# PX4FMUv2_4_6_3.net
KiCad netlist of a schematic drawn in Altium Designer
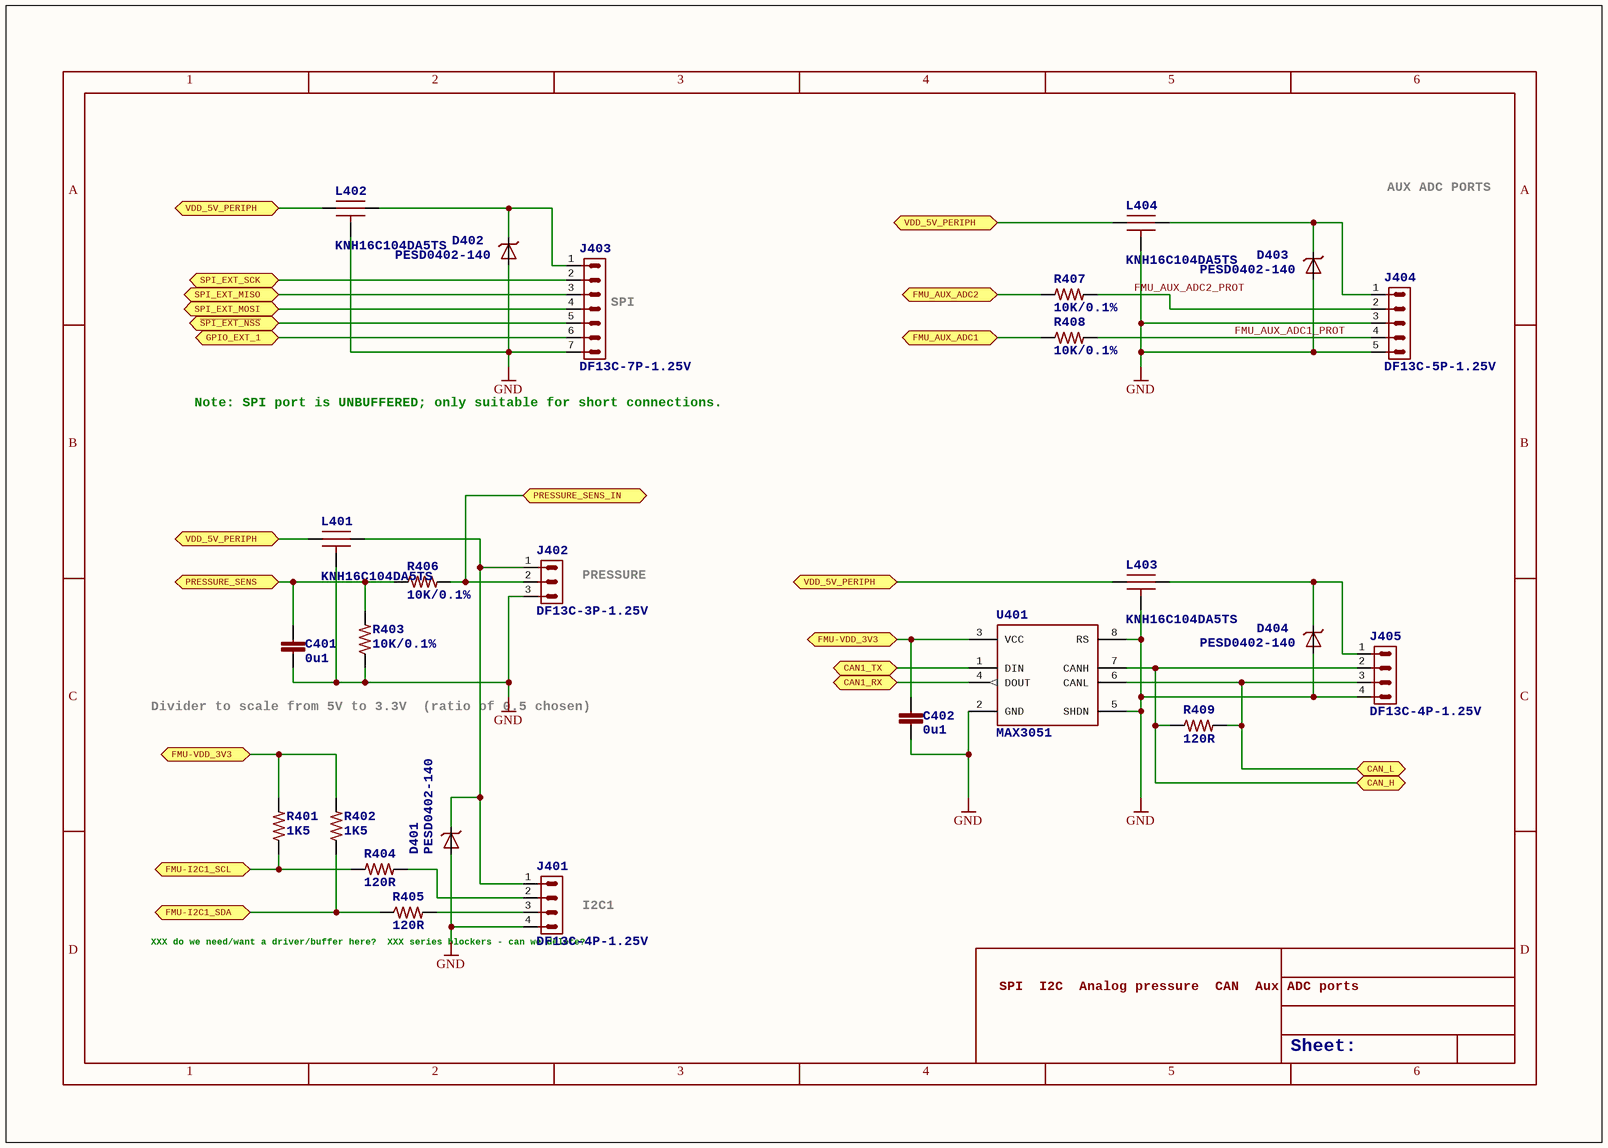
[diagram p0: PX4FMUv2.4.6_3.SchDoc]

(export (version "E")
  (design (tool "Eeschema 10.0.6"))
  (components
    (comp (ref "C401")
      (value "0u1")
      (footprint "0402-CAP")
      (description "CapacitorStandard 0603 ceramic capacitor, and 0.1\" leaded capacitor.")
      (fields (field (name "PARTNO") "CC0402ZRY5V7BB104"))
      (libsource (lib "pixhawk2") (part "CAP0402"))
    )
    (comp (ref "C402")
      (value "0u1")
      (footprint "0402-CAP")
      (description "CapacitorStandard 0603 ceramic capacitor, and 0.1\" leaded capacitor.")
      (fields (field (name "PARTNO") "CC0402ZRY5V7BB104"))
      (libsource (lib "pixhawk2") (part "CAP0402"))
    )
    (comp (ref "D401")
      (value "PESD0402-140")
      (footprint "0402-TVS")
      (libsource (lib "pixhawk2") (part "DIODE-TVS"))
    )
    (comp (ref "D402")
      (value "PESD0402-140")
      (footprint "0402-TVS")
      (libsource (lib "pixhawk2") (part "DIODE-TVS"))
    )
    (comp (ref "D403")
      (value "PESD0402-140")
      (footprint "0402-TVS")
      (libsource (lib "pixhawk2") (part "DIODE-TVS"))
    )
    (comp (ref "D404")
      (value "PESD0402-140")
      (footprint "0402-TVS")
      (libsource (lib "pixhawk2") (part "DIODE-TVS"))
    )
    (comp (ref "J401")
      (value "DF13C-4P-1.25V")
      (footprint "DF13C-4P-1.25V")
      (description "DF13-4P 1.25mm Pitch Miniature Crimping Connector.")
      (fields (field (name "PARTNO") "DF13C-4P-1.25V(20)"))
      (libsource (lib "con-hirose-df13") (part "DF13-4P-1.25V"))
    )
    (comp (ref "J402")
      (value "DF13C-3P-1.25V")
      (footprint "DF13C-3P-1.25V")
      (description "DF13-3P 1.25mm Pitch Miniature Crimping Connector.")
      (fields (field (name "PARTNO") "DF13C-3P-1.25V(20)"))
      (libsource (lib "con-hirose-df13") (part "DF13-3P-1.25V"))
    )
    (comp (ref "J403")
      (value "DF13C-7P-1.25V")
      (footprint "DF13C-7P-1.25V")
      (description "DF13-7P 1.25mm Pitch Miniature Crimping Connector.")
      (fields (field (name "PARTNO") "DF13C-7P-1.25V(20)"))
      (libsource (lib "con-hirose-df13") (part "DF13-7P-1.25V"))
    )
    (comp (ref "J404")
      (value "DF13C-5P-1.25V")
      (footprint "DF13C-5P-1.25V")
      (description "DF13-5P 1.25mm Pitch Miniature Crimping Connector.")
      (fields (field (name "PARTNO") "DF13C-5P-1.25V(20)"))
      (libsource (lib "con-hirose-df13") (part "DF13-5P-1.25V"))
    )
    (comp (ref "J405")
      (value "DF13C-4P-1.25V")
      (footprint "DF13C-4P-1.25V")
      (description "DF13-4P 1.25mm Pitch Miniature Crimping Connector.")
      (fields (field (name "PARTNO") "DF13C-4P-1.25V(20)"))
      (libsource (lib "con-hirose-df13") (part "DF13-4P-1.25V"))
    )
    (comp (ref "L401")
      (value "KNH16C104DA5TS")
      (footprint "KYOCERA-KNH16-DA")
      (description "Kyocera KNH16C104DA5TS EMI filter")
      (libsource (lib "pixhawk2") (part "KNH16C104DA5TS"))
    )
    (comp (ref "L402")
      (value "KNH16C104DA5TS")
      (footprint "KYOCERA-KNH16-DA")
      (description "Kyocera KNH16C104DA5TS EMI filter")
      (libsource (lib "pixhawk2") (part "KNH16C104DA5TS"))
    )
    (comp (ref "L403")
      (value "KNH16C104DA5TS")
      (footprint "KYOCERA-KNH16-DA")
      (description "Kyocera KNH16C104DA5TS EMI filter")
      (libsource (lib "pixhawk2") (part "KNH16C104DA5TS"))
    )
    (comp (ref "L404")
      (value "KNH16C104DA5TS")
      (footprint "KYOCERA-KNH16-DA")
      (description "Kyocera KNH16C104DA5TS EMI filter")
      (libsource (lib "pixhawk2") (part "KNH16C104DA5TS"))
    )
    (comp (ref "R401")
      (value "1K5")
      (footprint "0402-RES")
      (fields (field (name "PARTNO") "RC0402FR-071K5L"))
      (libsource (lib "pixhawk2") (part "RESISTOR0402-RES"))
    )
    (comp (ref "R402")
      (value "1K5")
      (footprint "0402-RES")
      (fields (field (name "PARTNO") "RC0402FR-071K5L"))
      (libsource (lib "pixhawk2") (part "RESISTOR0402-RES"))
    )
    (comp (ref "R403")
      (value "10K/0.1%")
      (footprint "0402-RES")
      (fields (field (name "PARTNO") "ERA-2AEB103X"))
      (libsource (lib "pixhawk2") (part "RESISTOR0402-RES"))
    )
    (comp (ref "R404")
      (value "120R")
      (footprint "0402-RES")
      (fields (field (name "PARTNO") "RC0402FR-07120RL"))
      (libsource (lib "pixhawk2") (part "RESISTOR0402-RES"))
    )
    (comp (ref "R405")
      (value "120R")
      (footprint "0402-RES")
      (fields (field (name "PARTNO") "RC0402FR-07120RL"))
      (libsource (lib "pixhawk2") (part "RESISTOR0402-RES"))
    )
    (comp (ref "R406")
      (value "10K/0.1%")
      (footprint "0402-RES")
      (fields (field (name "PARTNO") "ERA-2AEB103X"))
      (libsource (lib "pixhawk2") (part "RESISTOR0402-RES"))
    )
    (comp (ref "R407")
      (value "10K/0.1%")
      (footprint "0402-RES")
      (fields (field (name "PARTNO") "ERA-2AEB103X"))
      (libsource (lib "pixhawk2") (part "RESISTOR0402-RES"))
    )
    (comp (ref "R408")
      (value "10K/0.1%")
      (footprint "0402-RES")
      (fields (field (name "PARTNO") "ERA-2AEB103X"))
      (libsource (lib "pixhawk2") (part "RESISTOR0402-RES"))
    )
    (comp (ref "R409")
      (value "120R")
      (footprint "0402-RES")
      (fields (field (name "PARTNO") "RC0402FR-07120RL"))
      (libsource (lib "pixhawk2") (part "RESISTOR0402-RES"))
    )
    (comp (ref "U401")
      (value "MAX3051")
      (footprint "SOT23-8")
      (description "3.3-V CAN TRANSCEIVER")
      (fields (field (name "PARTNO") "MAX3051EKA"))
      (libsource (lib "pixhawk2") (part "MAX3051MAX3051EKA"))
    )
  )
  (nets
    (net (code "1") (name "/CAN1_RX") (class "Default")
      (node (ref "U401") (pin "4") (pinfunction "DOUT_4") (pintype "output"))
    )
    (net (code "2") (name "/CAN1_TX") (class "Default")
      (node (ref "U401") (pin "1") (pinfunction "DIN_1") (pintype "passive"))
    )
    (net (code "3") (name "/CAN_H") (class "Default")
      (node (ref "J405") (pin "2") (pinfunction "2_2") (pintype "passive"))
      (node (ref "R409") (pin "P$1") (pinfunction "1_P$1") (pintype "passive"))
      (node (ref "U401") (pin "7") (pinfunction "CANH_7") (pintype "passive"))
    )
    (net (code "4") (name "/CAN_L") (class "Default")
      (node (ref "J405") (pin "3") (pinfunction "3_3") (pintype "passive"))
      (node (ref "R409") (pin "P$2") (pinfunction "2_P$2") (pintype "passive"))
      (node (ref "U401") (pin "6") (pinfunction "CANL_6") (pintype "passive"))
    )
    (net (code "5") (name "/FMU-I2C1_SCL") (class "Default")
      (node (ref "R401") (pin "P$1") (pinfunction "1_P$1") (pintype "passive"))
      (node (ref "R404") (pin "P$1") (pinfunction "1_P$1") (pintype "passive"))
    )
    (net (code "6") (name "/FMU-I2C1_SDA") (class "Default")
      (node (ref "R402") (pin "P$1") (pinfunction "1_P$1") (pintype "passive"))
      (node (ref "R405") (pin "P$1") (pinfunction "1_P$1") (pintype "passive"))
    )
    (net (code "7") (name "/FMU-VDD_3V3") (class "Default")
      (node (ref "C402") (pin "P$1") (pinfunction "1_P$1") (pintype "passive"))
      (node (ref "R401") (pin "P$2") (pinfunction "2_P$2") (pintype "passive"))
      (node (ref "R402") (pin "P$2") (pinfunction "2_P$2") (pintype "passive"))
      (node (ref "U401") (pin "3") (pinfunction "VCC_3") (pintype "passive"))
    )
    (net (code "8") (name "/FMU_AUX_ADC1") (class "Default")
      (node (ref "R408") (pin "P$1") (pinfunction "1_P$1") (pintype "passive"))
    )
    (net (code "9") (name "/FMU_AUX_ADC1_PROT") (class "Default")
      (node (ref "J404") (pin "4") (pinfunction "4_4") (pintype "passive"))
      (node (ref "R408") (pin "P$2") (pinfunction "2_P$2") (pintype "passive"))
    )
    (net (code "10") (name "/FMU_AUX_ADC2") (class "Default")
      (node (ref "R407") (pin "P$1") (pinfunction "1_P$1") (pintype "passive"))
    )
    (net (code "11") (name "/FMU_AUX_ADC2_PROT") (class "Default")
      (node (ref "J404") (pin "2") (pinfunction "2_2") (pintype "passive"))
      (node (ref "R407") (pin "P$2") (pinfunction "2_P$2") (pintype "passive"))
    )
    (net (code "12") (name "/GPIO_EXT_1") (class "Default")
      (node (ref "J403") (pin "6") (pinfunction "6_6") (pintype "passive"))
    )
    (net (code "13") (name "/PRESSURE_SENS") (class "Default")
      (node (ref "C401") (pin "P$1") (pinfunction "1_P$1") (pintype "passive"))
      (node (ref "R403") (pin "P$2") (pinfunction "2_P$2") (pintype "passive"))
      (node (ref "R406") (pin "P$1") (pinfunction "1_P$1") (pintype "passive"))
    )
    (net (code "14") (name "/PRESSURE_SENS_IN") (class "Default")
      (node (ref "J402") (pin "2") (pinfunction "2_2") (pintype "passive"))
      (node (ref "R406") (pin "P$2") (pinfunction "2_P$2") (pintype "passive"))
    )
    (net (code "15") (name "/SPI_EXT_MISO") (class "Default")
      (node (ref "J403") (pin "3") (pinfunction "3_3") (pintype "passive"))
    )
    (net (code "16") (name "/SPI_EXT_MOSI") (class "Default")
      (node (ref "J403") (pin "4") (pinfunction "4_4") (pintype "passive"))
    )
    (net (code "17") (name "/SPI_EXT_SCK") (class "Default")
      (node (ref "J403") (pin "2") (pinfunction "2_2") (pintype "passive"))
    )
    (net (code "18") (name "/VDD_5V_PERIPH") (class "Default")
      (node (ref "L401") (pin "P$1") (pinfunction "P$1_P$1") (pintype "passive"))
      (node (ref "L402") (pin "P$1") (pinfunction "P$1_P$1") (pintype "passive"))
      (node (ref "L403") (pin "P$1") (pinfunction "P$1_P$1") (pintype "passive"))
      (node (ref "L404") (pin "P$1") (pinfunction "P$1_P$1") (pintype "passive"))
    )
    (net (code "19") (name "/~{SPI_EXT_NSS}") (class "Default")
      (node (ref "J403") (pin "5") (pinfunction "5_5") (pintype "passive"))
    )
    (net (code "20") (name "GND") (class "Default")
      (node (ref "C401") (pin "P$2") (pinfunction "2_P$2") (pintype "passive"))
      (node (ref "C402") (pin "P$2") (pinfunction "2_P$2") (pintype "passive"))
      (node (ref "D401") (pin "A") (pinfunction "A_A") (pintype "passive"))
      (node (ref "D402") (pin "A") (pinfunction "A_A") (pintype "passive"))
      (node (ref "D403") (pin "A") (pinfunction "A_A") (pintype "passive"))
      (node (ref "D404") (pin "A") (pinfunction "A_A") (pintype "passive"))
      (node (ref "J401") (pin "4") (pinfunction "4_4") (pintype "passive"))
      (node (ref "J402") (pin "3") (pinfunction "3_3") (pintype "passive"))
      (node (ref "J403") (pin "7") (pinfunction "7_7") (pintype "passive"))
      (node (ref "J404") (pin "3") (pinfunction "3_3") (pintype "passive"))
      (node (ref "J404") (pin "5") (pinfunction "5_5") (pintype "passive"))
      (node (ref "J405") (pin "4") (pinfunction "4_4") (pintype "passive"))
      (node (ref "L401") (pin "P$3_P$4_P$5") (pinfunction "P$3_P$3_P$4_P$5") (pintype "passive"))
      (node (ref "L402") (pin "P$3_P$4_P$5") (pinfunction "P$3_P$3_P$4_P$5") (pintype "passive"))
      (node (ref "L403") (pin "P$3_P$4_P$5") (pinfunction "P$3_P$3_P$4_P$5") (pintype "passive"))
      (node (ref "L404") (pin "P$3_P$4_P$5") (pinfunction "P$3_P$3_P$4_P$5") (pintype "passive"))
      (node (ref "R403") (pin "P$1") (pinfunction "1_P$1") (pintype "passive"))
      (node (ref "U401") (pin "2") (pinfunction "GND_2") (pintype "open_emitter"))
      (node (ref "U401") (pin "5") (pinfunction "SHDN_5") (pintype "passive"))
      (node (ref "U401") (pin "8") (pinfunction "RS_8") (pintype "passive"))
    )
    (net (code "21") (name "Net-(D401-PadC)") (class "Default")
      (node (ref "D401") (pin "C") (pinfunction "C_C") (pintype "passive"))
      (node (ref "J401") (pin "1") (pinfunction "1_1") (pintype "passive"))
      (node (ref "J402") (pin "1") (pinfunction "1_1") (pintype "passive"))
      (node (ref "L401") (pin "P$2") (pinfunction "P$2_P$2") (pintype "passive"))
    )
    (net (code "22") (name "Net-(D402-PadC)") (class "Default")
      (node (ref "D402") (pin "C") (pinfunction "C_C") (pintype "passive"))
      (node (ref "J403") (pin "1") (pinfunction "1_1") (pintype "passive"))
      (node (ref "L402") (pin "P$2") (pinfunction "P$2_P$2") (pintype "passive"))
    )
    (net (code "23") (name "Net-(D403-PadC)") (class "Default")
      (node (ref "D403") (pin "C") (pinfunction "C_C") (pintype "passive"))
      (node (ref "J404") (pin "1") (pinfunction "1_1") (pintype "passive"))
      (node (ref "L404") (pin "P$2") (pinfunction "P$2_P$2") (pintype "passive"))
    )
    (net (code "24") (name "Net-(D404-PadC)") (class "Default")
      (node (ref "D404") (pin "C") (pinfunction "C_C") (pintype "passive"))
      (node (ref "J405") (pin "1") (pinfunction "1_1") (pintype "passive"))
      (node (ref "L403") (pin "P$2") (pinfunction "P$2_P$2") (pintype "passive"))
    )
    (net (code "25") (name "Net-(R404-2)") (class "Default")
      (node (ref "J401") (pin "2") (pinfunction "2_2") (pintype "passive"))
      (node (ref "R404") (pin "P$2") (pinfunction "2_P$2") (pintype "passive"))
    )
    (net (code "26") (name "Net-(R405-2)") (class "Default")
      (node (ref "J401") (pin "3") (pinfunction "3_3") (pintype "passive"))
      (node (ref "R405") (pin "P$2") (pinfunction "2_P$2") (pintype "passive"))
    )
  )
)
